# MicroSD_Sniffer.net
KiCad netlist of a schematic drawn in EAGLE
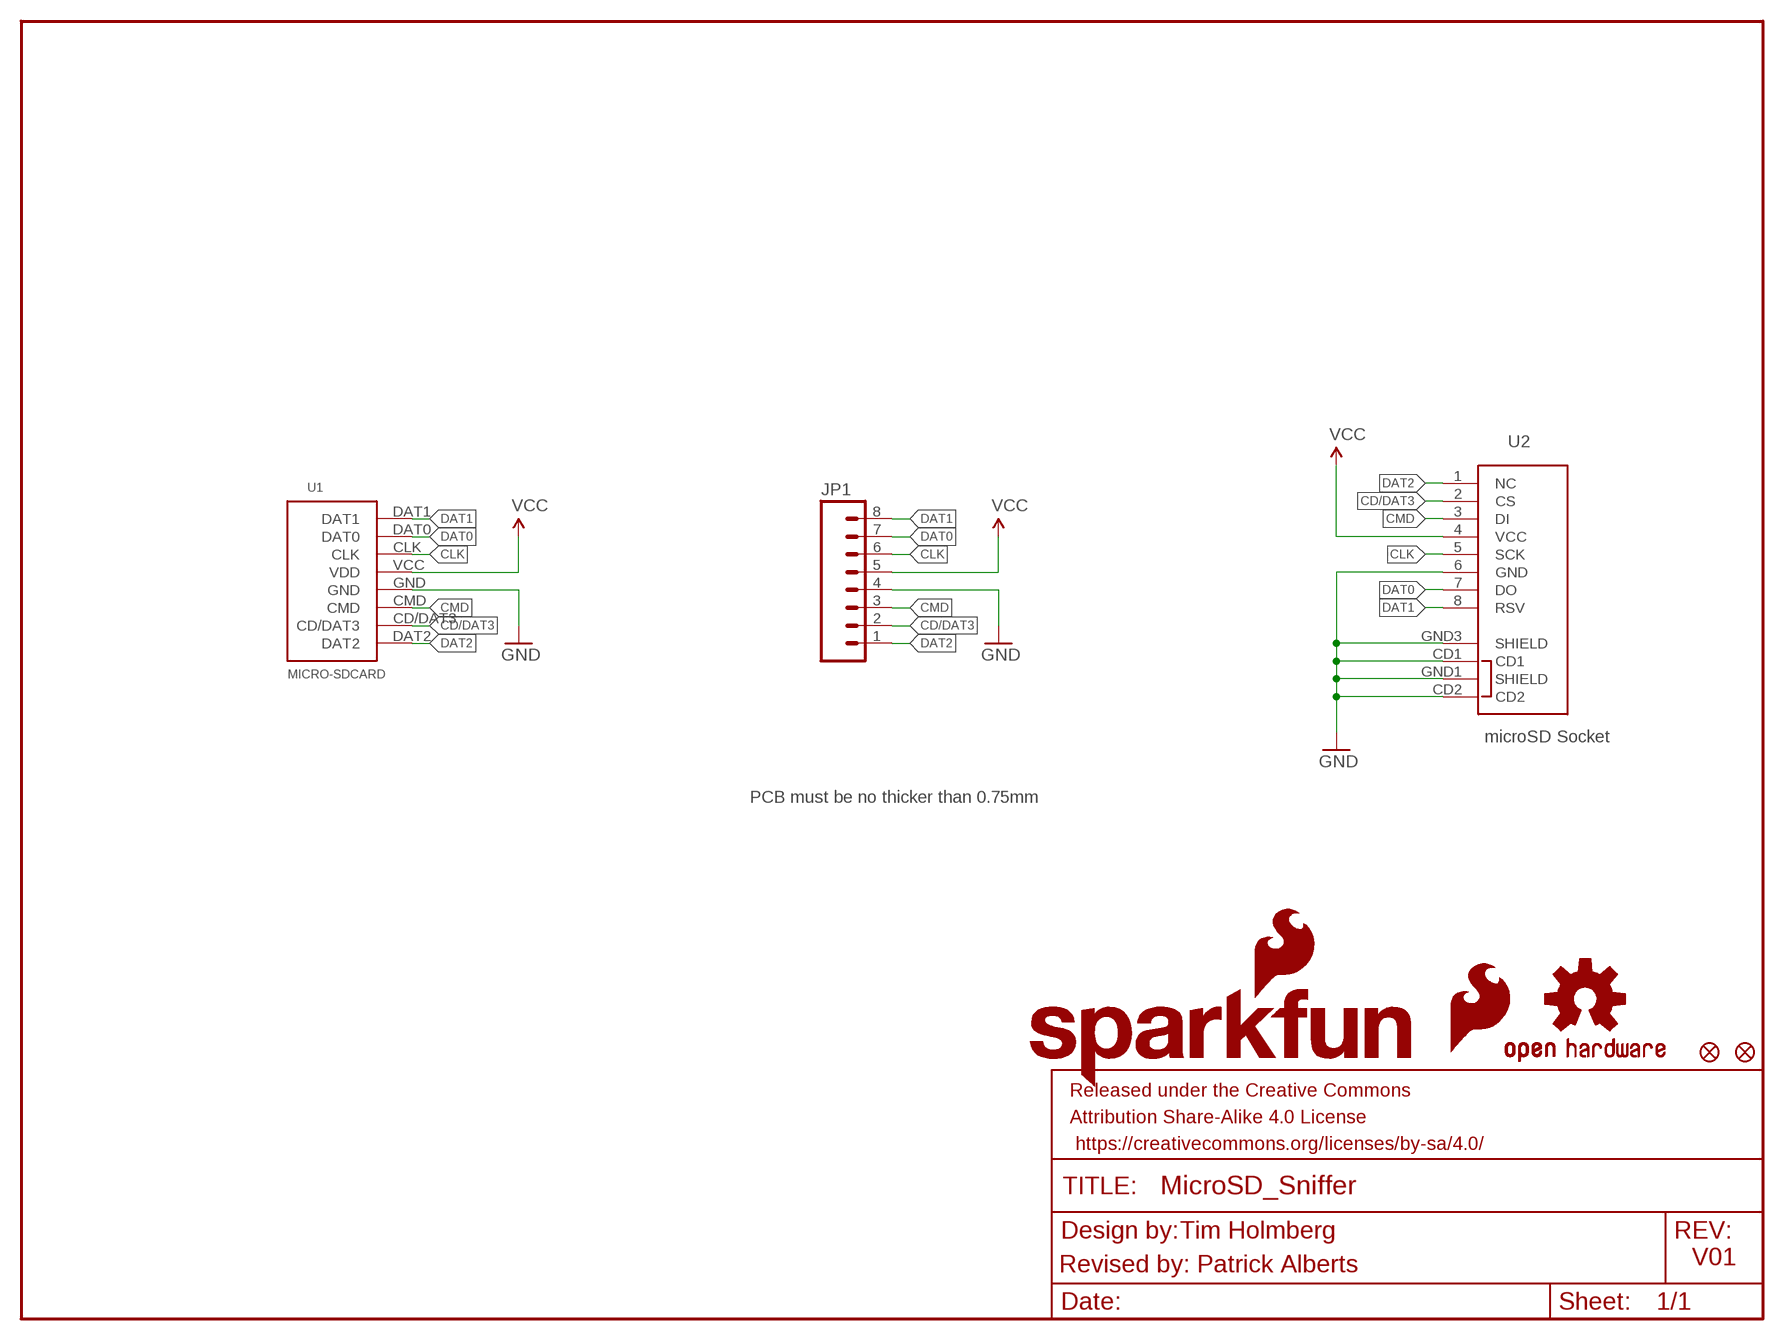
[diagram p0: schematic, sheet 1]

(export (version "E")
  (design (tool "Eeschema 10.0.6"))
  (components
    (comp (ref "FID1")
      (value "FIDUCIAL1X2")
      (footprint "eagle-import:FIDUCIAL-1X2")
      (libsource (lib "eagle-import") (part "FIDUCIAL1X2"))
    )
    (comp (ref "FID2")
      (value "FIDUCIAL1X2")
      (footprint "eagle-import:FIDUCIAL-1X2")
      (libsource (lib "eagle-import") (part "FIDUCIAL1X2"))
    )
    (comp (ref "FRAME1")
      (value "FRAME-LETTER")
      (footprint "eagle-import:CREATIVE_COMMONS")
      (fields (field (name "DESIGNER") "NAME"))
      (libsource (lib "eagle-import") (part "FRAME-LETTER"))
    )
    (comp (ref "JP1")
      (value "M08")
      (footprint "eagle-import:1X08")
      (libsource (lib "eagle-import") (part "M08"))
    )
    (comp (ref "LOGO1")
      (value "OSHW-LOGOM")
      (footprint "eagle-import:OSHW-LOGO-M")
      (libsource (lib "eagle-import") (part "OSHW-LOGOM"))
    )
    (comp (ref "LOGO2")
      (value "SFE_LOGO_FLAME.2_INCH")
      (footprint "eagle-import:SFE_LOGO_FLAME_.2")
      (libsource (lib "eagle-import") (part "SFE_LOGO_FLAME.2_INCH"))
    )
    (comp (ref "LOGO3")
      (value "SFE_LOGO_NAME_FLAME.1_INCH")
      (footprint "eagle-import:SFE_LOGO_NAME_FLAME_.1")
      (libsource (lib "eagle-import") (part "SFE_LOGO_NAME_FLAME.1_INCH"))
    )
    (comp (ref "U1")
      (value "MICRO-SDCARD")
      (footprint "eagle-import:MICRO-SDCARD")
      (libsource (lib "eagle-import") (part "MICRO-SDCARD"))
    )
    (comp (ref "U2")
      (value "microSD Socket")
      (footprint "eagle-import:MICROSD_1_1")
      (libsource (lib "eagle-import") (part "USD-SOCKET"))
    )
  )
  (nets
    (net (code "1") (name "CD{slash}DAT3") (class "Default")
      (node (ref "JP1") (pin "2") (pinfunction "2_2") (pintype "passive"))
      (node (ref "U1") (pin "CD/DAT3") (pinfunction "CD/DAT3_CD/DAT3") (pintype "bidirectional"))
      (node (ref "U2") (pin "2") (pinfunction "CS_2") (pintype "bidirectional"))
    )
    (net (code "2") (name "CLK") (class "Default")
      (node (ref "JP1") (pin "6") (pinfunction "6_6") (pintype "passive"))
      (node (ref "U1") (pin "CLK") (pinfunction "CLK_CLK") (pintype "bidirectional"))
      (node (ref "U2") (pin "5") (pinfunction "SCK_5") (pintype "bidirectional"))
    )
    (net (code "3") (name "CMD") (class "Default")
      (node (ref "JP1") (pin "3") (pinfunction "3_3") (pintype "passive"))
      (node (ref "U1") (pin "CMD") (pinfunction "CMD_CMD") (pintype "bidirectional"))
      (node (ref "U2") (pin "3") (pinfunction "DI_3") (pintype "bidirectional"))
    )
    (net (code "4") (name "DAT0") (class "Default")
      (node (ref "JP1") (pin "7") (pinfunction "7_7") (pintype "passive"))
      (node (ref "U1") (pin "DAT0") (pinfunction "DAT0_DAT0") (pintype "bidirectional"))
      (node (ref "U2") (pin "7") (pinfunction "DO_7") (pintype "bidirectional"))
    )
    (net (code "5") (name "DAT1") (class "Default")
      (node (ref "JP1") (pin "8") (pinfunction "8_8") (pintype "passive"))
      (node (ref "U1") (pin "DAT1") (pinfunction "DAT1_DAT1") (pintype "bidirectional"))
      (node (ref "U2") (pin "8") (pinfunction "RSV_8") (pintype "bidirectional"))
    )
    (net (code "6") (name "DAT2") (class "Default")
      (node (ref "JP1") (pin "1") (pinfunction "1_1") (pintype "passive"))
      (node (ref "U1") (pin "DAT2") (pinfunction "DAT2_DAT2") (pintype "bidirectional"))
      (node (ref "U2") (pin "1") (pinfunction "NC_1") (pintype "bidirectional"))
    )
    (net (code "7") (name "GND") (class "Default")
      (node (ref "JP1") (pin "4") (pinfunction "4_4") (pintype "passive"))
      (node (ref "U1") (pin "GND") (pinfunction "GND_GND") (pintype "bidirectional"))
      (node (ref "U2") (pin "6") (pinfunction "GND_6") (pintype "bidirectional"))
      (node (ref "U2") (pin "CD1") (pinfunction "CD1_CD1") (pintype "bidirectional"))
      (node (ref "U2") (pin "CD2") (pinfunction "CD2_CD2") (pintype "bidirectional"))
      (node (ref "U2") (pin "GND1") (pinfunction "SHIELD_GND1") (pintype "bidirectional"))
      (node (ref "U2") (pin "GND3") (pinfunction "SHIELD_GND3") (pintype "bidirectional"))
    )
    (net (code "8") (name "VCC") (class "Default")
      (node (ref "JP1") (pin "5") (pinfunction "5_5") (pintype "passive"))
      (node (ref "U1") (pin "VCC") (pinfunction "VDD_VCC") (pintype "bidirectional"))
      (node (ref "U2") (pin "4") (pinfunction "VCC_4") (pintype "bidirectional"))
    )
  )
)
